# KeypadHW10.net
KiCad netlist of a schematic drawn in Altium Designer
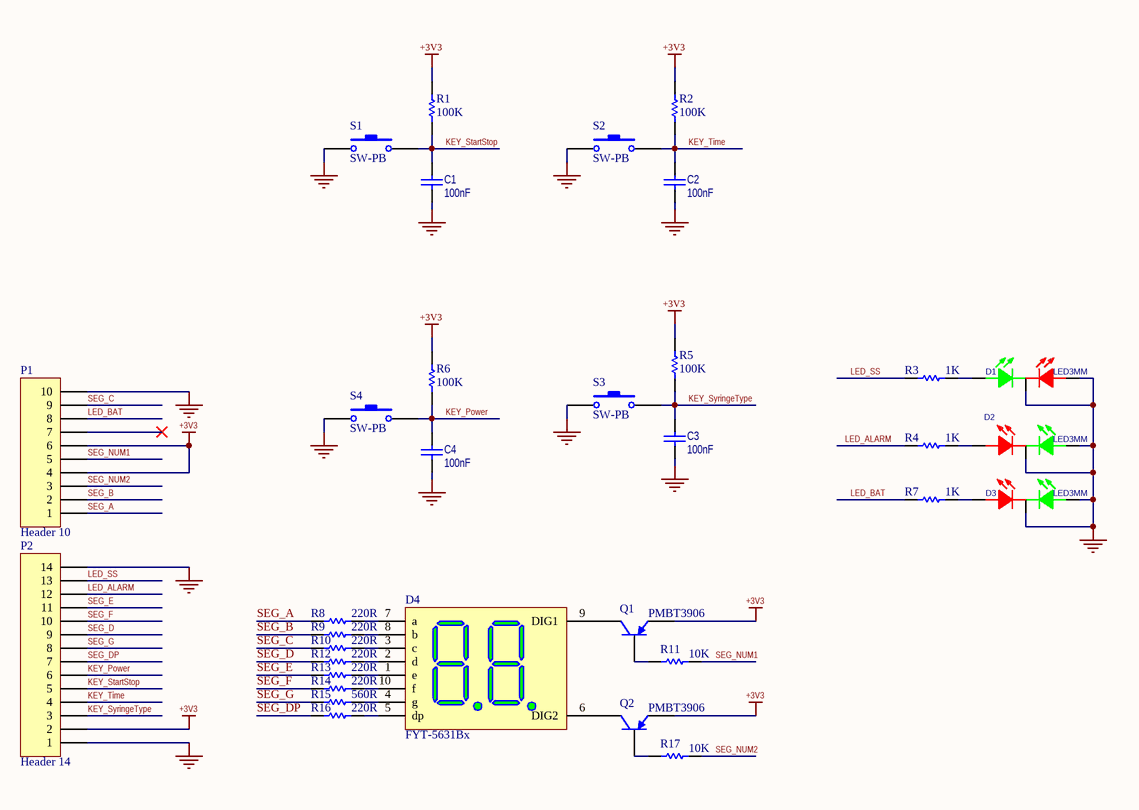
[diagram p0: KeypadHW10.SchDoc]

(export (version "E")
  (design (tool "Eeschema 10.0.6"))
  (components
    (comp (ref "C1")
      (value "100nF")
      (footprint "CAP0805")
      (description "Capacitor")
      (fields (field (name "PUBLISHER") "Altium Limited"))
      (libsource (lib "Miscellaneous Devices") (part "Cap"))
    )
    (comp (ref "C2")
      (value "100nF")
      (footprint "CAP0805")
      (description "Capacitor")
      (fields (field (name "PUBLISHER") "Altium Limited"))
      (libsource (lib "Miscellaneous Devices") (part "Cap"))
    )
    (comp (ref "C3")
      (value "100nF")
      (footprint "CAP0805")
      (description "Capacitor")
      (fields (field (name "PUBLISHER") "Altium Limited"))
      (libsource (lib "Miscellaneous Devices") (part "Cap"))
    )
    (comp (ref "C4")
      (value "100nF")
      (footprint "CAP0805")
      (description "Capacitor")
      (fields (field (name "PUBLISHER") "Altium Limited"))
      (libsource (lib "Miscellaneous Devices") (part "Cap"))
    )
    (comp (ref "D1")
      (value "LED3MM")
      (footprint "LED3MM_R&G")
      (description "LED BICOLOR CC")
      (fields (field (name "DESIGNER") "Abbas Basereh"))
      (libsource (lib "Mofidi3D") (part "LED_2C_CC"))
    )
    (comp (ref "D2")
      (value "LED3MM")
      (footprint "LED3MM_R&G")
      (description "LED BICOLOR CC")
      (fields (field (name "DESIGNER") "Abbas Basereh"))
      (libsource (lib "Mofidi3D") (part "LED_2C_CC"))
    )
    (comp (ref "D3")
      (value "LED3MM")
      (footprint "LED3MM_R&G")
      (description "LED BICOLOR CC")
      (fields (field (name "DESIGNER") "Abbas Basereh"))
      (libsource (lib "Mofidi3D") (part "LED_2C_CC"))
    )
    (comp (ref "D4")
      (value "FYT-5631Bx")
      (footprint "7SEG-2DIGIT-15x10")
      (description "CA-3digit-7Seg-10PIN")
      (libsource (lib "Mofidi3D") (part "7SEG-2DIGIT-10PIN"))
    )
    (comp (ref "P1")
      (value "Header 10")
      (footprint "HDR_1x10-2mm")
      (description "Header, 10-Pin")
      (fields (field (name "PUBLISHER") "Altium Limited"))
      (libsource (lib "Miscellaneous Connectors") (part "Header 10"))
    )
    (comp (ref "P2")
      (value "Header 14")
      (footprint "HDR_1x14-2mm")
      (description "Header, 14-Pin")
      (fields (field (name "PUBLISHER") "Altium Limited"))
      (libsource (lib "Miscellaneous Connectors") (part "Header 14"))
    )
    (comp (ref "Q1")
      (value "PMBT3906")
      (footprint "SOT23_N")
      (description "PNP Switching Transistor")
      (fields (field (name "PUBLISHER") "Altium Limited"))
      (libsource (lib "Philips Discrete BJT - Low Power") (part "PMBT3906"))
    )
    (comp (ref "Q2")
      (value "PMBT3906")
      (footprint "SOT23_N")
      (description "PNP Switching Transistor")
      (fields (field (name "PUBLISHER") "Altium Limited"))
      (libsource (lib "Philips Discrete BJT - Low Power") (part "PMBT3906"))
    )
    (comp (ref "R1")
      (value "100K")
      (footprint "RES0805")
      (description "Semiconductor Resistor")
      (fields (field (name "PUBLISHER") "Altium Limited"))
      (libsource (lib "Miscellaneous Devices") (part "Res Semi"))
    )
    (comp (ref "R2")
      (value "100K")
      (footprint "RES0805")
      (description "Semiconductor Resistor")
      (fields (field (name "PUBLISHER") "Altium Limited"))
      (libsource (lib "Miscellaneous Devices") (part "Res Semi"))
    )
    (comp (ref "R3")
      (value "1K")
      (footprint "RES0805")
      (description "Semiconductor Resistor")
      (fields (field (name "PUBLISHER") "Altium Limited"))
      (libsource (lib "Miscellaneous Devices") (part "Res Semi"))
    )
    (comp (ref "R4")
      (value "1K")
      (footprint "RES0805")
      (description "Semiconductor Resistor")
      (fields (field (name "PUBLISHER") "Altium Limited"))
      (libsource (lib "Miscellaneous Devices") (part "Res Semi"))
    )
    (comp (ref "R5")
      (value "100K")
      (footprint "RES0805")
      (description "Semiconductor Resistor")
      (fields (field (name "PUBLISHER") "Altium Limited"))
      (libsource (lib "Miscellaneous Devices") (part "Res Semi"))
    )
    (comp (ref "R6")
      (value "100K")
      (footprint "RES0805")
      (description "Semiconductor Resistor")
      (fields (field (name "PUBLISHER") "Altium Limited"))
      (libsource (lib "Miscellaneous Devices") (part "Res Semi"))
    )
    (comp (ref "R7")
      (value "1K")
      (footprint "RES0805")
      (description "Semiconductor Resistor")
      (fields (field (name "PUBLISHER") "Altium Limited"))
      (libsource (lib "Miscellaneous Devices") (part "Res Semi"))
    )
    (comp (ref "R8")
      (value "220R")
      (footprint "RES0805")
      (description "Semiconductor Resistor")
      (fields (field (name "PUBLISHER") "Altium Limited"))
      (libsource (lib "Miscellaneous Devices") (part "Res Semi"))
    )
    (comp (ref "R9")
      (value "220R")
      (footprint "RES0805")
      (description "Semiconductor Resistor")
      (fields (field (name "PUBLISHER") "Altium Limited"))
      (libsource (lib "Miscellaneous Devices") (part "Res Semi"))
    )
    (comp (ref "R10")
      (value "220R")
      (footprint "RES0805")
      (description "Semiconductor Resistor")
      (fields (field (name "PUBLISHER") "Altium Limited"))
      (libsource (lib "Miscellaneous Devices") (part "Res Semi"))
    )
    (comp (ref "R11")
      (value "10K")
      (footprint "RES0805")
      (description "Semiconductor Resistor")
      (fields (field (name "PUBLISHER") "Altium Limited"))
      (libsource (lib "Miscellaneous Devices") (part "Res Semi"))
    )
    (comp (ref "R12")
      (value "220R")
      (footprint "RES0805")
      (description "Semiconductor Resistor")
      (fields (field (name "PUBLISHER") "Altium Limited"))
      (libsource (lib "Miscellaneous Devices") (part "Res Semi"))
    )
    (comp (ref "R13")
      (value "220R")
      (footprint "RES0805")
      (description "Semiconductor Resistor")
      (fields (field (name "PUBLISHER") "Altium Limited"))
      (libsource (lib "Miscellaneous Devices") (part "Res Semi"))
    )
    (comp (ref "R14")
      (value "220R")
      (footprint "RES0805")
      (description "Semiconductor Resistor")
      (fields (field (name "PUBLISHER") "Altium Limited"))
      (libsource (lib "Miscellaneous Devices") (part "Res Semi"))
    )
    (comp (ref "R15")
      (value "560R")
      (footprint "RES0805")
      (description "Semiconductor Resistor")
      (fields (field (name "PUBLISHER") "Altium Limited"))
      (libsource (lib "Miscellaneous Devices") (part "Res Semi"))
    )
    (comp (ref "R16")
      (value "220R")
      (footprint "RES0805")
      (description "Semiconductor Resistor")
      (fields (field (name "PUBLISHER") "Altium Limited"))
      (libsource (lib "Miscellaneous Devices") (part "Res Semi"))
    )
    (comp (ref "R17")
      (value "10K")
      (footprint "RES0805")
      (description "Semiconductor Resistor")
      (fields (field (name "PUBLISHER") "Altium Limited"))
      (libsource (lib "Miscellaneous Devices") (part "Res Semi"))
    )
    (comp (ref "S1")
      (value "SW-PB")
      (footprint "SW-4PIN")
      (description "Switch")
      (fields (field (name "PUBLISHER") "Altium Limited"))
      (libsource (lib "Miscellaneous Devices") (part "SW-PB"))
    )
    (comp (ref "S2")
      (value "SW-PB")
      (footprint "SW-4PIN")
      (description "Switch")
      (fields (field (name "PUBLISHER") "Altium Limited"))
      (libsource (lib "Miscellaneous Devices") (part "SW-PB"))
    )
    (comp (ref "S3")
      (value "SW-PB")
      (footprint "SW-4PIN")
      (description "Switch")
      (fields (field (name "PUBLISHER") "Altium Limited"))
      (libsource (lib "Miscellaneous Devices") (part "SW-PB"))
    )
    (comp (ref "S4")
      (value "SW-PB")
      (footprint "SW-4PIN")
      (description "Switch")
      (fields (field (name "PUBLISHER") "Altium Limited"))
      (libsource (lib "Miscellaneous Devices") (part "SW-PB"))
    )
  )
  (nets
    (net (code "1") (name "+3V3") (class "Default")
      (node (ref "P1") (pin "4") (pinfunction "4_4") (pintype "passive"))
      (node (ref "P1") (pin "6") (pinfunction "6_6") (pintype "passive"))
      (node (ref "P2") (pin "2") (pinfunction "2_2") (pintype "passive"))
      (node (ref "Q1") (pin "2") (pinfunction "E_2") (pintype "passive"))
      (node (ref "Q2") (pin "2") (pinfunction "E_2") (pintype "passive"))
      (node (ref "R1") (pin "2") (pinfunction "2_2") (pintype "passive"))
      (node (ref "R2") (pin "2") (pinfunction "2_2") (pintype "passive"))
      (node (ref "R5") (pin "2") (pinfunction "2_2") (pintype "passive"))
      (node (ref "R6") (pin "2") (pinfunction "2_2") (pintype "passive"))
    )
    (net (code "2") (name "/KEY_Power") (class "Default")
      (node (ref "C4") (pin "2") (pinfunction "2_2") (pintype "passive"))
      (node (ref "P2") (pin "6") (pinfunction "6_6") (pintype "passive"))
      (node (ref "R6") (pin "1") (pinfunction "1_1") (pintype "passive"))
      (node (ref "S4") (pin "2") (pinfunction "2_2") (pintype "passive"))
    )
    (net (code "3") (name "/KEY_StartStop") (class "Default")
      (node (ref "C1") (pin "2") (pinfunction "2_2") (pintype "passive"))
      (node (ref "P2") (pin "5") (pinfunction "5_5") (pintype "passive"))
      (node (ref "R1") (pin "1") (pinfunction "1_1") (pintype "passive"))
      (node (ref "S1") (pin "2") (pinfunction "2_2") (pintype "passive"))
    )
    (net (code "4") (name "/KEY_SyringeType") (class "Default")
      (node (ref "C3") (pin "2") (pinfunction "2_2") (pintype "passive"))
      (node (ref "P2") (pin "3") (pinfunction "3_3") (pintype "passive"))
      (node (ref "R5") (pin "1") (pinfunction "1_1") (pintype "passive"))
      (node (ref "S3") (pin "2") (pinfunction "2_2") (pintype "passive"))
    )
    (net (code "5") (name "/KEY_Time") (class "Default")
      (node (ref "C2") (pin "2") (pinfunction "2_2") (pintype "passive"))
      (node (ref "P2") (pin "4") (pinfunction "4_4") (pintype "passive"))
      (node (ref "R2") (pin "1") (pinfunction "1_1") (pintype "passive"))
      (node (ref "S2") (pin "2") (pinfunction "2_2") (pintype "passive"))
    )
    (net (code "6") (name "/LED_ALARM") (class "Default")
      (node (ref "P2") (pin "12") (pinfunction "12_12") (pintype "passive"))
      (node (ref "R4") (pin "1") (pinfunction "1_1") (pintype "passive"))
    )
    (net (code "7") (name "/LED_BAT") (class "Default")
      (node (ref "P1") (pin "8") (pinfunction "8_8") (pintype "passive"))
      (node (ref "R7") (pin "1") (pinfunction "1_1") (pintype "passive"))
    )
    (net (code "8") (name "/LED_SS") (class "Default")
      (node (ref "P2") (pin "13") (pinfunction "13_13") (pintype "passive"))
      (node (ref "R3") (pin "1") (pinfunction "1_1") (pintype "passive"))
    )
    (net (code "9") (name "/SEG_A") (class "Default")
      (node (ref "P1") (pin "1") (pinfunction "1_1") (pintype "passive"))
      (node (ref "R8") (pin "1") (pinfunction "1_1") (pintype "passive"))
    )
    (net (code "10") (name "/SEG_B") (class "Default")
      (node (ref "P1") (pin "2") (pinfunction "2_2") (pintype "passive"))
      (node (ref "R9") (pin "1") (pinfunction "1_1") (pintype "passive"))
    )
    (net (code "11") (name "/SEG_C") (class "Default")
      (node (ref "P1") (pin "9") (pinfunction "9_9") (pintype "passive"))
      (node (ref "R10") (pin "1") (pinfunction "1_1") (pintype "passive"))
    )
    (net (code "12") (name "/SEG_D") (class "Default")
      (node (ref "P2") (pin "9") (pinfunction "9_9") (pintype "passive"))
      (node (ref "R12") (pin "1") (pinfunction "1_1") (pintype "passive"))
    )
    (net (code "13") (name "/SEG_DP") (class "Default")
      (node (ref "P2") (pin "7") (pinfunction "7_7") (pintype "passive"))
      (node (ref "R16") (pin "1") (pinfunction "1_1") (pintype "passive"))
    )
    (net (code "14") (name "/SEG_E") (class "Default")
      (node (ref "P2") (pin "11") (pinfunction "11_11") (pintype "passive"))
      (node (ref "R13") (pin "1") (pinfunction "1_1") (pintype "passive"))
    )
    (net (code "15") (name "/SEG_F") (class "Default")
      (node (ref "P2") (pin "10") (pinfunction "10_10") (pintype "passive"))
      (node (ref "R14") (pin "1") (pinfunction "1_1") (pintype "passive"))
    )
    (net (code "16") (name "/SEG_G") (class "Default")
      (node (ref "P2") (pin "8") (pinfunction "8_8") (pintype "passive"))
      (node (ref "R15") (pin "1") (pinfunction "1_1") (pintype "passive"))
    )
    (net (code "17") (name "/SEG_NUM1") (class "Default")
      (node (ref "P1") (pin "5") (pinfunction "5_5") (pintype "passive"))
      (node (ref "R11") (pin "2") (pinfunction "2_2") (pintype "passive"))
    )
    (net (code "18") (name "/SEG_NUM2") (class "Default")
      (node (ref "P1") (pin "3") (pinfunction "3_3") (pintype "passive"))
      (node (ref "R17") (pin "2") (pinfunction "2_2") (pintype "passive"))
    )
    (net (code "19") (name "GND") (class "Default")
      (node (ref "C1") (pin "1") (pinfunction "1_1") (pintype "passive"))
      (node (ref "C2") (pin "1") (pinfunction "1_1") (pintype "passive"))
      (node (ref "C3") (pin "1") (pinfunction "1_1") (pintype "passive"))
      (node (ref "C4") (pin "1") (pinfunction "1_1") (pintype "passive"))
      (node (ref "D1") (pin "2") (pinfunction "CATHODE_2") (pintype "passive"))
      (node (ref "D1") (pin "3") (pinfunction "ANODER_3") (pintype "passive"))
      (node (ref "D2") (pin "1") (pinfunction "ANODEG_1") (pintype "passive"))
      (node (ref "D2") (pin "2") (pinfunction "CATHODE_2") (pintype "passive"))
      (node (ref "D3") (pin "1") (pinfunction "ANODEG_1") (pintype "passive"))
      (node (ref "D3") (pin "2") (pinfunction "CATHODE_2") (pintype "passive"))
      (node (ref "P1") (pin "10") (pinfunction "10_10") (pintype "passive"))
      (node (ref "P2") (pin "1") (pinfunction "1_1") (pintype "passive"))
      (node (ref "P2") (pin "14") (pinfunction "14_14") (pintype "passive"))
      (node (ref "S1") (pin "1") (pinfunction "1_1") (pintype "passive"))
      (node (ref "S2") (pin "1") (pinfunction "1_1") (pintype "passive"))
      (node (ref "S3") (pin "1") (pinfunction "1_1") (pintype "passive"))
      (node (ref "S4") (pin "1") (pinfunction "1_1") (pintype "passive"))
    )
    (net (code "20") (name "Net-(D1-ANODEG)") (class "Default")
      (node (ref "D1") (pin "1") (pinfunction "ANODEG_1") (pintype "passive"))
      (node (ref "R3") (pin "2") (pinfunction "2_2") (pintype "passive"))
    )
    (net (code "21") (name "Net-(D2-ANODER)") (class "Default")
      (node (ref "D2") (pin "3") (pinfunction "ANODER_3") (pintype "passive"))
      (node (ref "R4") (pin "2") (pinfunction "2_2") (pintype "passive"))
    )
    (net (code "22") (name "Net-(D3-ANODER)") (class "Default")
      (node (ref "D3") (pin "3") (pinfunction "ANODER_3") (pintype "passive"))
      (node (ref "R7") (pin "2") (pinfunction "2_2") (pintype "passive"))
    )
    (net (code "23") (name "Net-(D4-DIG1)") (class "Default")
      (node (ref "D4") (pin "9") (pinfunction "DIG1_9") (pintype "passive"))
      (node (ref "Q1") (pin "3") (pinfunction "C_3") (pintype "passive"))
    )
    (net (code "24") (name "Net-(D4-DIG2)") (class "Default")
      (node (ref "D4") (pin "6") (pinfunction "DIG2_6") (pintype "passive"))
      (node (ref "Q2") (pin "3") (pinfunction "C_3") (pintype "passive"))
    )
    (net (code "25") (name "Net-(D4-a)") (class "Default")
      (node (ref "D4") (pin "7") (pinfunction "a_7") (pintype "passive"))
      (node (ref "R8") (pin "2") (pinfunction "2_2") (pintype "passive"))
    )
    (net (code "26") (name "Net-(D4-b)") (class "Default")
      (node (ref "D4") (pin "8") (pinfunction "b_8") (pintype "passive"))
      (node (ref "R9") (pin "2") (pinfunction "2_2") (pintype "passive"))
    )
    (net (code "27") (name "Net-(D4-c)") (class "Default")
      (node (ref "D4") (pin "3") (pinfunction "c_3") (pintype "passive"))
      (node (ref "R10") (pin "2") (pinfunction "2_2") (pintype "passive"))
    )
    (net (code "28") (name "Net-(D4-d)") (class "Default")
      (node (ref "D4") (pin "2") (pinfunction "d_2") (pintype "passive"))
      (node (ref "R12") (pin "2") (pinfunction "2_2") (pintype "passive"))
    )
    (net (code "29") (name "Net-(D4-dp)") (class "Default")
      (node (ref "D4") (pin "5") (pinfunction "dp_5") (pintype "passive"))
      (node (ref "R16") (pin "2") (pinfunction "2_2") (pintype "passive"))
    )
    (net (code "30") (name "Net-(D4-e)") (class "Default")
      (node (ref "D4") (pin "1") (pinfunction "e_1") (pintype "passive"))
      (node (ref "R13") (pin "2") (pinfunction "2_2") (pintype "passive"))
    )
    (net (code "31") (name "Net-(D4-f)") (class "Default")
      (node (ref "D4") (pin "10") (pinfunction "f_10") (pintype "passive"))
      (node (ref "R14") (pin "2") (pinfunction "2_2") (pintype "passive"))
    )
    (net (code "32") (name "Net-(D4-g)") (class "Default")
      (node (ref "D4") (pin "4") (pinfunction "g_4") (pintype "passive"))
      (node (ref "R15") (pin "2") (pinfunction "2_2") (pintype "passive"))
    )
    (net (code "33") (name "Net-(Q1-B)") (class "Default")
      (node (ref "Q1") (pin "1") (pinfunction "B_1") (pintype "passive"))
      (node (ref "R11") (pin "1") (pinfunction "1_1") (pintype "passive"))
    )
    (net (code "34") (name "Net-(Q2-B)") (class "Default")
      (node (ref "Q2") (pin "1") (pinfunction "B_1") (pintype "passive"))
      (node (ref "R17") (pin "1") (pinfunction "1_1") (pintype "passive"))
    )
    (net (code "35") (name "unconnected-(P1-Pad7)") (class "Default")
      (node (ref "P1") (pin "7") (pinfunction "7_7") (pintype "passive+no_connect"))
    )
  )
)
